# schematic.net
KiCad netlist of a schematic drawn in Altium Designer
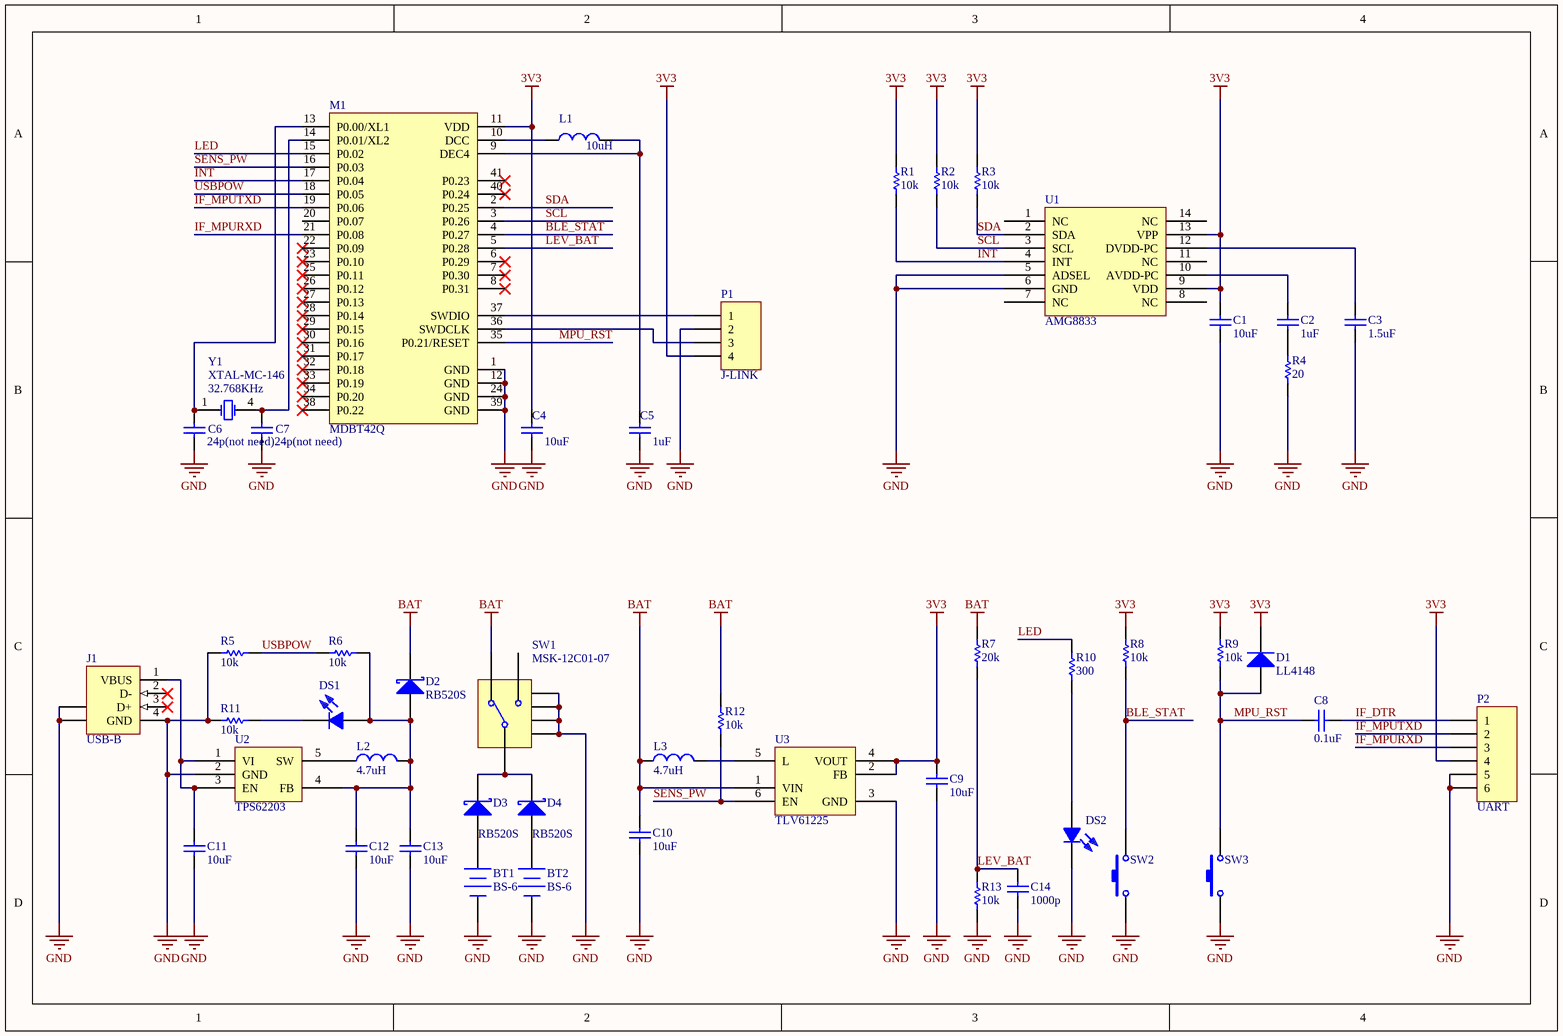
[diagram p0: schematic.SchDoc]

(export (version "E")
  (design (tool "Eeschema 10.0.6"))
  (components
    (comp (ref "BT1")
      (value "BS-6")
      (footprint "BS-6")
      (fields (field (name "PUBLISHER") "Altium Limited"))
      (libsource (lib "Module") (part "BS-6"))
    )
    (comp (ref "BT2")
      (value "BS-6")
      (footprint "BS-6")
      (fields (field (name "PUBLISHER") "Altium Limited"))
      (libsource (lib "Module") (part "BS-6"))
    )
    (comp (ref "C1")
      (value "10uF")
      (footprint "2012[0805]")
      (fields (field (name "Comment") "Cap1"))
      (libsource (lib "Other") (part "Cap1"))
    )
    (comp (ref "C2")
      (value "1uF")
      (footprint "2012[0805]")
      (fields (field (name "Comment") "Cap1"))
      (libsource (lib "Other") (part "Cap1"))
    )
    (comp (ref "C3")
      (value "1.5uF")
      (footprint "2012[0805]")
      (fields (field (name "Comment") "Cap1"))
      (libsource (lib "Other") (part "Cap1"))
    )
    (comp (ref "C4")
      (value "10uF")
      (footprint "2012[0805]")
      (fields (field (name "Comment") "Cap1"))
      (libsource (lib "Other") (part "Cap1"))
    )
    (comp (ref "C5")
      (value "1uF")
      (footprint "2012[0805]")
      (fields (field (name "Comment") "Cap1"))
      (libsource (lib "Other") (part "Cap1"))
    )
    (comp (ref "C6")
      (value "24p(not need)")
      (footprint "2012[0805]")
      (fields (field (name "Comment") "Cap1"))
      (libsource (lib "Other") (part "Cap1"))
    )
    (comp (ref "C7")
      (value "24p(not need)")
      (footprint "2012[0805]")
      (fields (field (name "Comment") "Cap1"))
      (libsource (lib "Other") (part "Cap1"))
    )
    (comp (ref "C8")
      (value "0.1uF")
      (footprint "2012[0805]")
      (fields (field (name "Comment") "Cap1"))
      (libsource (lib "Other") (part "Cap1"))
    )
    (comp (ref "C9")
      (value "10uF")
      (footprint "2012[0805]")
      (fields (field (name "Comment") "Cap1"))
      (libsource (lib "Other") (part "Cap1"))
    )
    (comp (ref "C10")
      (value "10uF")
      (footprint "2012[0805]")
      (fields (field (name "Comment") "Cap1"))
      (libsource (lib "Other") (part "Cap1"))
    )
    (comp (ref "C11")
      (value "10uF")
      (footprint "2012[0805]")
      (fields (field (name "Comment") "Cap1"))
      (libsource (lib "Other") (part "Cap1"))
    )
    (comp (ref "C12")
      (value "10uF")
      (footprint "2012[0805]")
      (fields (field (name "Comment") "Cap1"))
      (libsource (lib "Other") (part "Cap1"))
    )
    (comp (ref "C13")
      (value "10uF")
      (footprint "2012[0805]")
      (fields (field (name "Comment") "Cap1"))
      (libsource (lib "Other") (part "Cap1"))
    )
    (comp (ref "C14")
      (value "1000p")
      (footprint "2012[0805]")
      (fields (field (name "Comment") "Cap1"))
      (libsource (lib "Other") (part "Cap1"))
    )
    (comp (ref "D1") (value "LL4148") (footprint "SOD80") (libsource (lib "Diode") (part "LL4148")))
    (comp (ref "D2") (value "RB520S") (footprint "SC-79") (libsource (lib "Diode") (part "RB520S")))
    (comp (ref "D3") (value "RB520S") (footprint "SC-79") (libsource (lib "Diode") (part "RB520S")))
    (comp (ref "D4") (value "RB520S") (footprint "SC-79") (libsource (lib "Diode") (part "RB520S")))
    (comp (ref "DS1") (value "~") (footprint "3216[1206]+A") (libsource (lib "Optical") (part "LED")))
    (comp (ref "DS2") (value "~") (footprint "3216[1206]+A") (libsource (lib "Optical") (part "LED")))
    (comp (ref "J1")
      (value "USB-B")
      (footprint "USB-B-MICRO")
      (description "USB 1.1, Right Angle, Thru-Hole, B Type, Receptacle, 4 Position, White")
      (fields (field (name "PUBLISHER") "Altium Limited"))
      (libsource (lib "Connector") (part "USB-B"))
    )
    (comp (ref "L1")
      (value "10uH")
      (footprint "2012[0805]")
      (fields (field (name "Comment") "Inductor"))
      (libsource (lib "Other") (part "Inductor"))
    )
    (comp (ref "L2")
      (value "4.7uH")
      (footprint "2012[0805]")
      (fields (field (name "Comment") "Inductor"))
      (libsource (lib "Other") (part "Inductor"))
    )
    (comp (ref "L3")
      (value "4.7uH")
      (footprint "2012[0805]")
      (fields (field (name "Comment") "Inductor"))
      (libsource (lib "Other") (part "Inductor"))
    )
    (comp (ref "M1") (value "MDBT42Q") (footprint "MDBT42Q") (libsource (lib "Module") (part "MDBT42Q")))
    (comp (ref "P1")
      (value "J-LINK")
      (footprint "HDR1X4")
      (description "Header, 4-Pin")
      (fields (field (name "PUBLISHER") "Altium Limited"))
      (libsource (lib "Connector") (part "Header 4"))
    )
    (comp (ref "P2")
      (value "UART")
      (footprint "HDR1X6")
      (description "Header, 6-Pin")
      (fields (field (name "PUBLISHER") "Altium Limited"))
      (libsource (lib "Connector") (part "Header 6"))
    )
    (comp (ref "R1")
      (value "10k")
      (footprint "2012[0805]")
      (fields (field (name "Comment") "Res"))
      (libsource (lib "Other") (part "Res"))
    )
    (comp (ref "R2")
      (value "10k")
      (footprint "2012[0805]")
      (fields (field (name "Comment") "Res"))
      (libsource (lib "Other") (part "Res"))
    )
    (comp (ref "R3")
      (value "10k")
      (footprint "2012[0805]")
      (fields (field (name "Comment") "Res"))
      (libsource (lib "Other") (part "Res"))
    )
    (comp (ref "R4")
      (value "20")
      (footprint "2012[0805]")
      (fields (field (name "Comment") "Res"))
      (libsource (lib "Other") (part "Res"))
    )
    (comp (ref "R5")
      (value "10k")
      (footprint "2012[0805]")
      (fields (field (name "Comment") "Res"))
      (libsource (lib "Other") (part "Res"))
    )
    (comp (ref "R6")
      (value "10k")
      (footprint "2012[0805]")
      (fields (field (name "Comment") "Res"))
      (libsource (lib "Other") (part "Res"))
    )
    (comp (ref "R7")
      (value "20k")
      (footprint "2012[0805]")
      (fields (field (name "Comment") "Res"))
      (libsource (lib "Other") (part "Res"))
    )
    (comp (ref "R8")
      (value "10k")
      (footprint "2012[0805]")
      (fields (field (name "Comment") "Res"))
      (libsource (lib "Other") (part "Res"))
    )
    (comp (ref "R9")
      (value "10k")
      (footprint "2012[0805]")
      (fields (field (name "Comment") "Res"))
      (libsource (lib "Other") (part "Res"))
    )
    (comp (ref "R10")
      (value "300")
      (footprint "2012[0805]")
      (fields (field (name "Comment") "Res"))
      (libsource (lib "Other") (part "Res"))
    )
    (comp (ref "R11")
      (value "10k")
      (footprint "2012[0805]")
      (fields (field (name "Comment") "Res"))
      (libsource (lib "Other") (part "Res"))
    )
    (comp (ref "R12")
      (value "10k")
      (footprint "2012[0805]")
      (fields (field (name "Comment") "Res"))
      (libsource (lib "Other") (part "Res"))
    )
    (comp (ref "R13")
      (value "10k")
      (footprint "2012[0805]")
      (fields (field (name "Comment") "Res"))
      (libsource (lib "Other") (part "Res"))
    )
    (comp (ref "SW1")
      (value "MSK-12C01-07")
      (footprint "MSK-12C01-07")
      (libsource (lib "Switch") (part "MSK-12C01-07"))
    )
    (comp (ref "SW2")
      (value "TL3342F160QG")
      (footprint "TL3342F160QG")
      (libsource (lib "Switch") (part "TL3342F160QG"))
    )
    (comp (ref "SW3")
      (value "TL3342F160QG")
      (footprint "TL3342F160QG")
      (libsource (lib "Switch") (part "TL3342F160QG"))
    )
    (comp (ref "U1") (value "AMG8833") (footprint "AMG8833") (libsource (lib "Sensor") (part "AMG8833")))
    (comp (ref "U2") (value "TPS62203") (footprint "SOT23-5") (libsource (lib "Power") (part "TPS62203")))
    (comp (ref "U3") (value "TLV61225") (footprint "SC72-6") (libsource (lib "Power") (part "TLV61225")))
    (comp (ref "Y1")
      (value "XTAL-MC-146")
      (footprint "MC-146")
      (fields (field (name "ALTIUM_VALUE") "32.768KHz"))
      (libsource (lib "Signal") (part "XTAL-MC-146"))
    )
  )
  (nets
    (net (code "1") (name "/BLE_STAT") (class "Default")
      (node (ref "M1") (pin "4") (pinfunction "P0.27_4") (pintype "passive"))
      (node (ref "R8") (pin "2") (pinfunction "2_2") (pintype "passive"))
      (node (ref "SW2") (pin "3") (pinfunction "3_3") (pintype "passive"))
    )
    (net (code "2") (name "/IF_DTR") (class "Default")
      (node (ref "C8") (pin "1") (pinfunction "1_1") (pintype "passive"))
      (node (ref "P2") (pin "1") (pinfunction "1_1") (pintype "passive"))
    )
    (net (code "3") (name "/IF_MPURXD") (class "Default")
      (node (ref "M1") (pin "21") (pinfunction "P0.08_21") (pintype "passive"))
      (node (ref "P2") (pin "3") (pinfunction "3_3") (pintype "passive"))
    )
    (net (code "4") (name "/IF_MPUTXD") (class "Default")
      (node (ref "M1") (pin "19") (pinfunction "P0.06_19") (pintype "passive"))
      (node (ref "P2") (pin "2") (pinfunction "2_2") (pintype "passive"))
    )
    (net (code "5") (name "/INT") (class "Default")
      (node (ref "M1") (pin "17") (pinfunction "P0.04_17") (pintype "passive"))
      (node (ref "R1") (pin "1") (pinfunction "1_1") (pintype "passive"))
      (node (ref "U1") (pin "4") (pinfunction "INT_4") (pintype "passive"))
    )
    (net (code "6") (name "/LED") (class "Default")
      (node (ref "M1") (pin "15") (pinfunction "P0.02_15") (pintype "passive"))
      (node (ref "R10") (pin "1") (pinfunction "1_1") (pintype "passive"))
    )
    (net (code "7") (name "/LEV_BAT") (class "Default")
      (node (ref "C14") (pin "1") (pinfunction "1_1") (pintype "passive"))
      (node (ref "M1") (pin "5") (pinfunction "P0.28_5") (pintype "passive"))
      (node (ref "R13") (pin "1") (pinfunction "1_1") (pintype "passive"))
      (node (ref "R7") (pin "2") (pinfunction "2_2") (pintype "passive"))
    )
    (net (code "8") (name "/MPU_RST") (class "Default")
      (node (ref "C8") (pin "2") (pinfunction "2_2") (pintype "passive"))
      (node (ref "D1") (pin "1") (pinfunction "A_1") (pintype "passive"))
      (node (ref "M1") (pin "35") (pinfunction "P0.21/RESET_35") (pintype "passive"))
      (node (ref "R9") (pin "2") (pinfunction "2_2") (pintype "passive"))
      (node (ref "SW3") (pin "3") (pinfunction "3_3") (pintype "passive"))
    )
    (net (code "9") (name "/SCL") (class "Default")
      (node (ref "M1") (pin "3") (pinfunction "P0.26_3") (pintype "passive"))
      (node (ref "R2") (pin "1") (pinfunction "1_1") (pintype "passive"))
      (node (ref "U1") (pin "3") (pinfunction "SCL_3") (pintype "passive"))
    )
    (net (code "10") (name "/SDA") (class "Default")
      (node (ref "M1") (pin "2") (pinfunction "P0.25_2") (pintype "passive"))
      (node (ref "R3") (pin "1") (pinfunction "1_1") (pintype "passive"))
      (node (ref "U1") (pin "2") (pinfunction "SDA_2") (pintype "passive"))
    )
    (net (code "11") (name "/SENS_PW") (class "Default")
      (node (ref "M1") (pin "16") (pinfunction "P0.03_16") (pintype "passive"))
      (node (ref "R12") (pin "1") (pinfunction "1_1") (pintype "passive"))
      (node (ref "U3") (pin "6") (pinfunction "EN_6") (pintype "passive"))
    )
    (net (code "12") (name "/USBPOW") (class "Default")
      (node (ref "M1") (pin "18") (pinfunction "P0.05_18") (pintype "passive"))
      (node (ref "R5") (pin "1") (pinfunction "1_1") (pintype "passive"))
      (node (ref "R6") (pin "2") (pinfunction "2_2") (pintype "passive"))
    )
    (net (code "13") (name "3V3") (class "Default")
      (node (ref "C1") (pin "2") (pinfunction "2_2") (pintype "passive"))
      (node (ref "C4") (pin "2") (pinfunction "2_2") (pintype "passive"))
      (node (ref "C9") (pin "2") (pinfunction "2_2") (pintype "passive"))
      (node (ref "D1") (pin "2") (pinfunction "K_2") (pintype "passive"))
      (node (ref "M1") (pin "11") (pinfunction "VDD_11") (pintype "passive"))
      (node (ref "P1") (pin "4") (pinfunction "4_4") (pintype "passive"))
      (node (ref "P2") (pin "4") (pinfunction "4_4") (pintype "passive"))
      (node (ref "R1") (pin "2") (pinfunction "2_2") (pintype "passive"))
      (node (ref "R2") (pin "2") (pinfunction "2_2") (pintype "passive"))
      (node (ref "R3") (pin "2") (pinfunction "2_2") (pintype "passive"))
      (node (ref "R8") (pin "1") (pinfunction "1_1") (pintype "passive"))
      (node (ref "R9") (pin "1") (pinfunction "1_1") (pintype "passive"))
      (node (ref "U1") (pin "13") (pinfunction "VPP_13") (pintype "passive"))
      (node (ref "U1") (pin "9") (pinfunction "VDD_9") (pintype "passive"))
      (node (ref "U3") (pin "2") (pinfunction "FB_2") (pintype "passive"))
      (node (ref "U3") (pin "4") (pinfunction "VOUT_4") (pintype "passive"))
    )
    (net (code "14") (name "BAT") (class "Default")
      (node (ref "C10") (pin "2") (pinfunction "2_2") (pintype "passive"))
      (node (ref "D2") (pin "2") (pinfunction "K_2") (pintype "passive"))
      (node (ref "L3") (pin "1") (pinfunction "1_1") (pintype "passive"))
      (node (ref "R12") (pin "2") (pinfunction "2_2") (pintype "passive"))
      (node (ref "R7") (pin "1") (pinfunction "1_1") (pintype "passive"))
      (node (ref "SW1") (pin "1") (pinfunction "1_1") (pintype "passive"))
      (node (ref "U3") (pin "1") (pinfunction "VIN_1") (pintype "passive"))
    )
    (net (code "15") (name "GND") (class "Default")
      (node (ref "BT1") (pin "2") (pinfunction "-_2") (pintype "passive"))
      (node (ref "BT2") (pin "2") (pinfunction "-_2") (pintype "passive"))
      (node (ref "C1") (pin "1") (pinfunction "1_1") (pintype "passive"))
      (node (ref "C10") (pin "1") (pinfunction "1_1") (pintype "passive"))
      (node (ref "C11") (pin "1") (pinfunction "1_1") (pintype "passive"))
      (node (ref "C12") (pin "1") (pinfunction "1_1") (pintype "passive"))
      (node (ref "C13") (pin "1") (pinfunction "1_1") (pintype "passive"))
      (node (ref "C14") (pin "2") (pinfunction "2_2") (pintype "passive"))
      (node (ref "C3") (pin "1") (pinfunction "1_1") (pintype "passive"))
      (node (ref "C4") (pin "1") (pinfunction "1_1") (pintype "passive"))
      (node (ref "C5") (pin "1") (pinfunction "1_1") (pintype "passive"))
      (node (ref "C6") (pin "1") (pinfunction "1_1") (pintype "passive"))
      (node (ref "C7") (pin "1") (pinfunction "1_1") (pintype "passive"))
      (node (ref "C9") (pin "1") (pinfunction "1_1") (pintype "passive"))
      (node (ref "DS2") (pin "2") (pintype "passive"))
      (node (ref "J1") (pin "4") (pinfunction "GND_4") (pintype "power_in"))
      (node (ref "J1") (pin "5") (pinfunction "SHLD_5") (pintype "passive"))
      (node (ref "J1") (pin "6") (pinfunction "SHLD_6") (pintype "passive"))
      (node (ref "M1") (pin "1") (pinfunction "GND_1") (pintype "passive"))
      (node (ref "M1") (pin "12") (pinfunction "GND_12") (pintype "passive"))
      (node (ref "M1") (pin "24") (pinfunction "GND_24") (pintype "passive"))
      (node (ref "M1") (pin "39") (pinfunction "GND_39") (pintype "passive"))
      (node (ref "P1") (pin "2") (pinfunction "2_2") (pintype "passive"))
      (node (ref "P2") (pin "5") (pinfunction "5_5") (pintype "passive"))
      (node (ref "P2") (pin "6") (pinfunction "6_6") (pintype "passive"))
      (node (ref "R11") (pin "2") (pinfunction "2_2") (pintype "passive"))
      (node (ref "R13") (pin "2") (pinfunction "2_2") (pintype "passive"))
      (node (ref "R4") (pin "1") (pinfunction "1_1") (pintype "passive"))
      (node (ref "R5") (pin "2") (pinfunction "2_2") (pintype "passive"))
      (node (ref "SW1") (pin "4") (pinfunction "4_4") (pintype "passive"))
      (node (ref "SW1") (pin "5") (pinfunction "5_5") (pintype "passive"))
      (node (ref "SW1") (pin "6") (pinfunction "6_6") (pintype "passive"))
      (node (ref "SW1") (pin "7") (pinfunction "7_7") (pintype "passive"))
      (node (ref "SW2") (pin "1") (pinfunction "1_1") (pintype "passive"))
      (node (ref "SW3") (pin "1") (pinfunction "1_1") (pintype "passive"))
      (node (ref "U1") (pin "5") (pinfunction "ADSEL_5") (pintype "passive"))
      (node (ref "U1") (pin "6") (pinfunction "GND_6") (pintype "passive"))
      (node (ref "U2") (pin "2") (pinfunction "GND_2") (pintype "passive"))
      (node (ref "U3") (pin "3") (pinfunction "GND_3") (pintype "passive"))
    )
    (net (code "16") (name "Net-(BT1-+)") (class "Default")
      (node (ref "BT1") (pin "1") (pinfunction "+_1") (pintype "passive"))
      (node (ref "D3") (pin "1") (pinfunction "A_1") (pintype "passive"))
    )
    (net (code "17") (name "Net-(BT2-+)") (class "Default")
      (node (ref "BT2") (pin "1") (pinfunction "+_1") (pintype "passive"))
      (node (ref "D4") (pin "1") (pinfunction "A_1") (pintype "passive"))
    )
    (net (code "18") (name "Net-(C2-Pad1)") (class "Default")
      (node (ref "C2") (pin "1") (pinfunction "1_1") (pintype "passive"))
      (node (ref "R4") (pin "2") (pinfunction "2_2") (pintype "passive"))
    )
    (net (code "19") (name "Net-(D2-A)") (class "Default")
      (node (ref "C12") (pin "2") (pinfunction "2_2") (pintype "passive"))
      (node (ref "C13") (pin "2") (pinfunction "2_2") (pintype "passive"))
      (node (ref "D2") (pin "1") (pinfunction "A_1") (pintype "passive"))
      (node (ref "DS1") (pin "1") (pintype "passive"))
      (node (ref "L2") (pin "2") (pinfunction "2_2") (pintype "passive"))
      (node (ref "R6") (pin "1") (pinfunction "1_1") (pintype "passive"))
      (node (ref "U2") (pin "4") (pinfunction "FB_4") (pintype "passive"))
    )
    (net (code "20") (name "Net-(D3-K)") (class "Default")
      (node (ref "D3") (pin "2") (pinfunction "K_2") (pintype "passive"))
      (node (ref "D4") (pin "2") (pinfunction "K_2") (pintype "passive"))
      (node (ref "SW1") (pin "2") (pinfunction "2_2") (pintype "passive"))
    )
    (net (code "21") (name "Net-(DS1-Pad2)") (class "Default")
      (node (ref "DS1") (pin "2") (pintype "passive"))
      (node (ref "R11") (pin "1") (pinfunction "1_1") (pintype "passive"))
    )
    (net (code "22") (name "Net-(DS2-Pad1)") (class "Default")
      (node (ref "DS2") (pin "1") (pintype "passive"))
      (node (ref "R10") (pin "2") (pinfunction "2_2") (pintype "passive"))
    )
    (net (code "23") (name "Net-(J1-VBUS)") (class "Default")
      (node (ref "C11") (pin "2") (pinfunction "2_2") (pintype "passive"))
      (node (ref "J1") (pin "1") (pinfunction "VBUS_1") (pintype "power_in"))
      (node (ref "U2") (pin "1") (pinfunction "VI_1") (pintype "passive"))
      (node (ref "U2") (pin "3") (pinfunction "EN_3") (pintype "passive"))
    )
    (net (code "24") (name "Net-(M1-DCC)") (class "Default")
      (node (ref "L1") (pin "1") (pinfunction "1_1") (pintype "passive"))
      (node (ref "M1") (pin "10") (pinfunction "DCC_10") (pintype "passive"))
    )
    (net (code "25") (name "Net-(M1-DEC4)") (class "Default")
      (node (ref "C5") (pin "2") (pinfunction "2_2") (pintype "passive"))
      (node (ref "L1") (pin "2") (pinfunction "2_2") (pintype "passive"))
      (node (ref "M1") (pin "9") (pinfunction "DEC4_9") (pintype "passive"))
    )
    (net (code "26") (name "Net-(M1-P0.00{slash}XL1)") (class "Default")
      (node (ref "C6") (pin "2") (pinfunction "2_2") (pintype "passive"))
      (node (ref "M1") (pin "13") (pinfunction "P0.00/XL1_13") (pintype "passive"))
      (node (ref "Y1") (pin "1") (pinfunction "OSC1_1") (pintype "passive"))
    )
    (net (code "27") (name "Net-(M1-P0.01{slash}XL2)") (class "Default")
      (node (ref "C7") (pin "2") (pinfunction "2_2") (pintype "passive"))
      (node (ref "M1") (pin "14") (pinfunction "P0.01/XL2_14") (pintype "passive"))
      (node (ref "Y1") (pin "4") (pinfunction "OSC2_4") (pintype "passive"))
    )
    (net (code "28") (name "Net-(M1-SWDCLK)") (class "Default")
      (node (ref "M1") (pin "36") (pinfunction "SWDCLK_36") (pintype "passive"))
      (node (ref "P1") (pin "3") (pinfunction "3_3") (pintype "passive"))
    )
    (net (code "29") (name "Net-(M1-SWDIO)") (class "Default")
      (node (ref "M1") (pin "37") (pinfunction "SWDIO_37") (pintype "passive"))
      (node (ref "P1") (pin "1") (pinfunction "1_1") (pintype "passive"))
    )
    (net (code "30") (name "Net-(U1-AVDD-PC)") (class "Default")
      (node (ref "C2") (pin "2") (pinfunction "2_2") (pintype "passive"))
      (node (ref "U1") (pin "10") (pinfunction "AVDD-PC_10") (pintype "passive"))
    )
    (net (code "31") (name "Net-(U1-DVDD-PC)") (class "Default")
      (node (ref "C3") (pin "2") (pinfunction "2_2") (pintype "passive"))
      (node (ref "U1") (pin "12") (pinfunction "DVDD-PC_12") (pintype "passive"))
    )
    (net (code "32") (name "Net-(U2-SW)") (class "Default")
      (node (ref "L2") (pin "1") (pinfunction "1_1") (pintype "passive"))
      (node (ref "U2") (pin "5") (pinfunction "SW_5") (pintype "passive"))
    )
    (net (code "33") (name "Net-(U3-L)") (class "Default")
      (node (ref "L3") (pin "2") (pinfunction "2_2") (pintype "passive"))
      (node (ref "U3") (pin "5") (pinfunction "L_5") (pintype "passive"))
    )
    (net (code "34") (name "unconnected-(J1-D+-Pad3)") (class "Default")
      (node (ref "J1") (pin "3") (pinfunction "D+_3") (pintype "input+no_connect"))
    )
    (net (code "35") (name "unconnected-(J1-D--Pad2)") (class "Default")
      (node (ref "J1") (pin "2") (pinfunction "D-_2") (pintype "input+no_connect"))
    )
    (net (code "36") (name "unconnected-(M1-P0.07-Pad20)") (class "Default")
      (node (ref "M1") (pin "20") (pinfunction "P0.07_20") (pintype "passive"))
    )
    (net (code "37") (name "unconnected-(M1-P0.09-Pad22)") (class "Default")
      (node (ref "M1") (pin "22") (pinfunction "P0.09_22") (pintype "passive+no_connect"))
    )
    (net (code "38") (name "unconnected-(M1-P0.10-Pad23)") (class "Default")
      (node (ref "M1") (pin "23") (pinfunction "P0.10_23") (pintype "passive+no_connect"))
    )
    (net (code "39") (name "unconnected-(M1-P0.11-Pad25)") (class "Default")
      (node (ref "M1") (pin "25") (pinfunction "P0.11_25") (pintype "passive+no_connect"))
    )
    (net (code "40") (name "unconnected-(M1-P0.12-Pad26)") (class "Default")
      (node (ref "M1") (pin "26") (pinfunction "P0.12_26") (pintype "passive+no_connect"))
    )
    (net (code "41") (name "unconnected-(M1-P0.13-Pad27)") (class "Default")
      (node (ref "M1") (pin "27") (pinfunction "P0.13_27") (pintype "passive+no_connect"))
    )
    (net (code "42") (name "unconnected-(M1-P0.14-Pad28)") (class "Default")
      (node (ref "M1") (pin "28") (pinfunction "P0.14_28") (pintype "passive+no_connect"))
    )
    (net (code "43") (name "unconnected-(M1-P0.15-Pad29)") (class "Default")
      (node (ref "M1") (pin "29") (pinfunction "P0.15_29") (pintype "passive+no_connect"))
    )
    (net (code "44") (name "unconnected-(M1-P0.16-Pad30)") (class "Default")
      (node (ref "M1") (pin "30") (pinfunction "P0.16_30") (pintype "passive+no_connect"))
    )
    (net (code "45") (name "unconnected-(M1-P0.17-Pad31)") (class "Default")
      (node (ref "M1") (pin "31") (pinfunction "P0.17_31") (pintype "passive+no_connect"))
    )
    (net (code "46") (name "unconnected-(M1-P0.18-Pad32)") (class "Default")
      (node (ref "M1") (pin "32") (pinfunction "P0.18_32") (pintype "passive+no_connect"))
    )
    (net (code "47") (name "unconnected-(M1-P0.19-Pad33)") (class "Default")
      (node (ref "M1") (pin "33") (pinfunction "P0.19_33") (pintype "passive+no_connect"))
    )
    (net (code "48") (name "unconnected-(M1-P0.20-Pad34)") (class "Default")
      (node (ref "M1") (pin "34") (pinfunction "P0.20_34") (pintype "passive+no_connect"))
    )
    (net (code "49") (name "unconnected-(M1-P0.22-Pad38)") (class "Default")
      (node (ref "M1") (pin "38") (pinfunction "P0.22_38") (pintype "passive+no_connect"))
    )
    (net (code "50") (name "unconnected-(M1-P0.23-Pad41)") (class "Default")
      (node (ref "M1") (pin "41") (pinfunction "P0.23_41") (pintype "passive+no_connect"))
    )
    (net (code "51") (name "unconnected-(M1-P0.24-Pad40)") (class "Default")
      (node (ref "M1") (pin "40") (pinfunction "P0.24_40") (pintype "passive+no_connect"))
    )
    (net (code "52") (name "unconnected-(M1-P0.29-Pad6)") (class "Default")
      (node (ref "M1") (pin "6") (pinfunction "P0.29_6") (pintype "passive+no_connect"))
    )
    (net (code "53") (name "unconnected-(M1-P0.30-Pad7)") (class "Default")
      (node (ref "M1") (pin "7") (pinfunction "P0.30_7") (pintype "passive+no_connect"))
    )
    (net (code "54") (name "unconnected-(M1-P0.31-Pad8)") (class "Default")
      (node (ref "M1") (pin "8") (pinfunction "P0.31_8") (pintype "passive+no_connect"))
    )
    (net (code "55") (name "unconnected-(SW1-Pad3)") (class "Default")
      (node (ref "SW1") (pin "3") (pinfunction "3_3") (pintype "passive"))
    )
    (net (code "56") (name "unconnected-(U1-NC-Pad1)") (class "Default")
      (node (ref "U1") (pin "1") (pinfunction "NC_1") (pintype "passive"))
    )
    (net (code "57") (name "unconnected-(U1-NC-Pad7)") (class "Default")
      (node (ref "U1") (pin "7") (pinfunction "NC_7") (pintype "passive"))
    )
    (net (code "58") (name "unconnected-(U1-NC-Pad8)") (class "Default")
      (node (ref "U1") (pin "8") (pinfunction "NC_8") (pintype "passive"))
    )
    (net (code "59") (name "unconnected-(U1-NC-Pad11)") (class "Default")
      (node (ref "U1") (pin "11") (pinfunction "NC_11") (pintype "passive"))
    )
    (net (code "60") (name "unconnected-(U1-NC-Pad14)") (class "Default")
      (node (ref "U1") (pin "14") (pinfunction "NC_14") (pintype "passive"))
    )
  )
)
